# Raspberry_etherIO_v1.net
KiCad netlist of a schematic drawn in Altium Designer
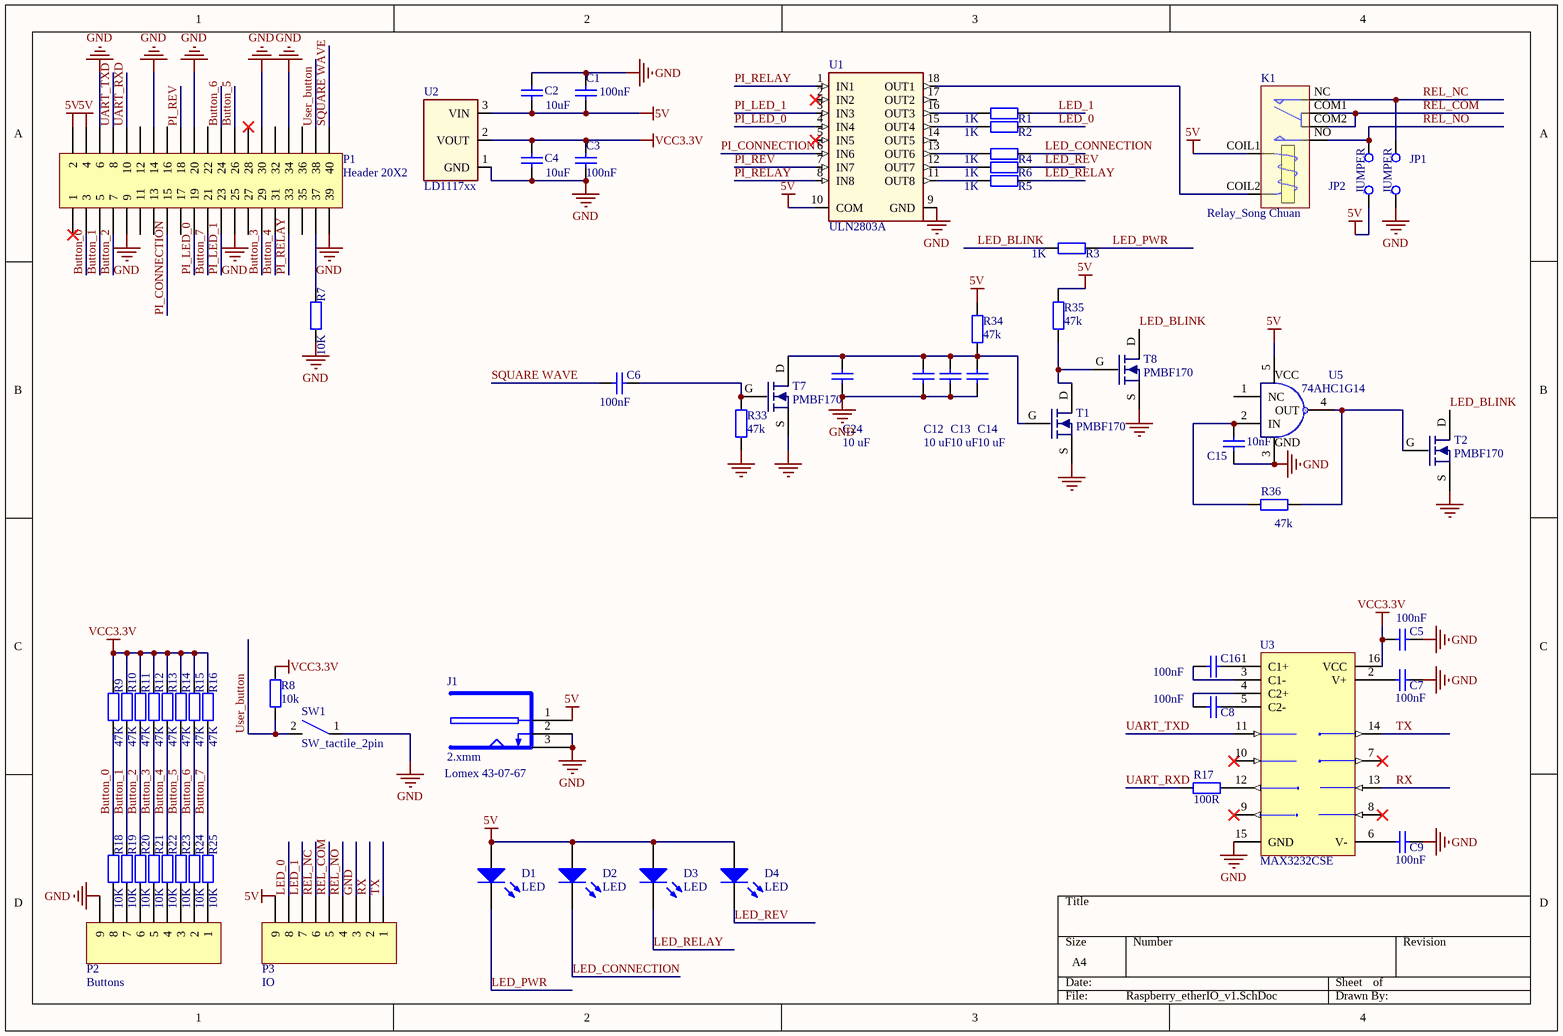
[diagram p0: Raspberry_etherIO_v1.SchDoc]

(export (version "E")
  (design (tool "Eeschema 10.0.6"))
  (components
    (comp (ref "C1")
      (value "100nF")
      (footprint "FP_0603_CAP_080")
      (description "Capacitor")
      (fields (field (name "PUBLISHER") "Altium Limited"))
      (libsource (lib "Miscellaneous Devices") (part "Cap"))
    )
    (comp (ref "C2")
      (value "10uF")
      (footprint "FP_1206_CAP_085")
      (description "Capacitor")
      (fields (field (name "PUBLISHER") "Altium Limited"))
      (libsource (lib "Miscellaneous Devices") (part "Cap"))
    )
    (comp (ref "C3")
      (value "100nF")
      (footprint "FP_0603_CAP_080")
      (description "Capacitor")
      (fields (field (name "PUBLISHER") "Altium Limited"))
      (libsource (lib "Miscellaneous Devices") (part "Cap"))
    )
    (comp (ref "C4")
      (value "10uF")
      (footprint "FP_1206_CAP_085")
      (description "Capacitor")
      (fields (field (name "PUBLISHER") "Altium Limited"))
      (libsource (lib "Miscellaneous Devices") (part "Cap"))
    )
    (comp (ref "C5")
      (value "100nF")
      (footprint "FP_0603_CAP_080")
      (description "Capacitor")
      (libsource (lib "Capacitor") (part "CAP"))
    )
    (comp (ref "C6")
      (value "100nF")
      (footprint "FP_0603_CAP_080")
      (description "Capacitor")
      (libsource (lib "Capacitor") (part "CAP"))
    )
    (comp (ref "C7")
      (value "100nF")
      (footprint "FP_0603_CAP_080")
      (description "Capacitor")
      (libsource (lib "Capacitor") (part "CAP"))
    )
    (comp (ref "C8")
      (value "100nF")
      (footprint "FP_0603_CAP_080")
      (description "Capacitor")
      (libsource (lib "Capacitor") (part "CAP"))
    )
    (comp (ref "C9")
      (value "100nF")
      (footprint "FP_0603_CAP_080")
      (description "Capacitor")
      (libsource (lib "Capacitor") (part "CAP"))
    )
    (comp (ref "C12")
      (value "10 uF")
      (footprint "FP_1210_CAP_N")
      (description "Capacitor")
      (libsource (lib "Capacitor") (part "CAP"))
    )
    (comp (ref "C13")
      (value "10 uF")
      (footprint "FP_1210_CAP_N")
      (description "Capacitor")
      (libsource (lib "Capacitor") (part "CAP"))
    )
    (comp (ref "C14")
      (value "10 uF")
      (footprint "FP_1210_CAP_N")
      (description "Capacitor")
      (libsource (lib "Capacitor") (part "CAP"))
    )
    (comp (ref "C15")
      (value "10nF")
      (footprint "FP_0603_CAP_080")
      (description "Capacitor")
      (fields (field (name "PUBLISHER") "Altium Limited"))
      (libsource (lib "Miscellaneous Devices") (part "Cap"))
    )
    (comp (ref "C16")
      (value "100nF")
      (footprint "FP_0603_CAP_080")
      (description "Capacitor")
      (libsource (lib "Capacitor") (part "CAP"))
    )
    (comp (ref "C24")
      (value "10 uF")
      (footprint "FP_1210_CAP_N")
      (description "Capacitor")
      (libsource (lib "Capacitor") (part "CAP"))
    )
    (comp (ref "D1")
      (value "LED")
      (footprint "1206 LED Reversed")
      (description "Typical LED")
      (libsource (lib "Led_optical") (part "LED"))
    )
    (comp (ref "D2")
      (value "LED")
      (footprint "1206 LED Reversed")
      (description "Typical LED")
      (libsource (lib "Led_optical") (part "LED"))
    )
    (comp (ref "D3")
      (value "LED")
      (footprint "1206 LED Reversed")
      (description "Typical LED")
      (libsource (lib "Led_optical") (part "LED"))
    )
    (comp (ref "D4")
      (value "LED")
      (footprint "1206 LED Reversed")
      (description "Typical LED")
      (libsource (lib "Led_optical") (part "LED"))
    )
    (comp (ref "J1")
      (value "2.xmm")
      (footprint "FP_DC_TAP_ANYA")
      (description "2.xmm DC HEBA25 TÁPFESZÜLTSÉG ALJZAT ZÁRT, NYÁKBA 90°")
      (fields (field (name "ORDER INFO") "Lomex 43-07-67"))
      (libsource (lib "Connector") (part "DC_TAP_ANYA"))
    )
    (comp (ref "JP1")
      (value "JUMPER")
      (footprint "FP_CONN2_TUSKE_254MM")
      (description "Jumper Wire")
      (libsource (lib "Other") (part "JUMPER"))
    )
    (comp (ref "JP2")
      (value "JUMPER")
      (footprint "FP_CONN2_TUSKE_254MM")
      (description "Jumper Wire")
      (libsource (lib "Other") (part "JUMPER"))
    )
    (comp (ref "K1")
      (value "Relay_Song Chuan")
      (footprint "Relay_Song Chuan")
      (description "SPDT Relay")
      (fields (field (name "PUBLISHER") "Altium Limited"))
      (libsource (lib "Switch") (part "Relay_Song Chuan"))
    )
    (comp (ref "P1")
      (value "Header 20X2")
      (footprint "Header_2X20_pin_2.54")
      (description "Header, 20-Pin, Dual row")
      (fields (field (name "PUBLISHER") "Altium Limited"))
      (libsource (lib "Miscellaneous Connectors") (part "Header 20X2"))
    )
    (comp (ref "P2")
      (value "Buttons")
      (footprint "Euroblock 3.5pitch 9P")
      (description "Header, 9-Pin")
      (fields (field (name "PUBLISHER") "Altium Limited"))
      (libsource (lib "Miscellaneous Connectors") (part "Header 9"))
    )
    (comp (ref "P3")
      (value "IO")
      (footprint "Euroblock 3.5pitch 9P")
      (description "Header, 9-Pin")
      (fields (field (name "PUBLISHER") "Altium Limited"))
      (libsource (lib "Miscellaneous Connectors") (part "Header 9"))
    )
    (comp (ref "R1")
      (value "1K")
      (footprint "FP_0603_RES")
      (description "Resistor")
      (libsource (lib "") (part "RES_2"))
    )
    (comp (ref "R2")
      (value "1K")
      (footprint "FP_0603_RES")
      (description "Resistor")
      (libsource (lib "") (part "RES_2"))
    )
    (comp (ref "R3")
      (value "1K")
      (footprint "FP_0603_RES")
      (description "Resistor")
      (libsource (lib "") (part "RES_2"))
    )
    (comp (ref "R4")
      (value "1K")
      (footprint "FP_0603_RES")
      (description "Resistor")
      (libsource (lib "") (part "RES_2"))
    )
    (comp (ref "R5")
      (value "1K")
      (footprint "FP_0603_RES")
      (description "Resistor")
      (libsource (lib "") (part "RES_2"))
    )
    (comp (ref "R6")
      (value "1K")
      (footprint "FP_0603_RES")
      (description "Resistor")
      (libsource (lib "") (part "RES_2"))
    )
    (comp (ref "R7")
      (value "10K")
      (footprint "FP_0603_RES")
      (description "Resistor")
      (libsource (lib "Resistor") (part "RES"))
    )
    (comp (ref "R8")
      (value "10k")
      (footprint "FP_0603_RES")
      (description "Resistor")
      (libsource (lib "") (part "RES_3"))
    )
    (comp (ref "R9")
      (value "47K")
      (footprint "FP_0603_RES")
      (description "Resistor")
      (libsource (lib "Resistor") (part "RES"))
    )
    (comp (ref "R10")
      (value "47K")
      (footprint "FP_0603_RES")
      (description "Resistor")
      (libsource (lib "Resistor") (part "RES"))
    )
    (comp (ref "R11")
      (value "47K")
      (footprint "FP_0603_RES")
      (description "Resistor")
      (libsource (lib "Resistor") (part "RES"))
    )
    (comp (ref "R12")
      (value "47K")
      (footprint "FP_0603_RES")
      (description "Resistor")
      (libsource (lib "Resistor") (part "RES"))
    )
    (comp (ref "R13")
      (value "47K")
      (footprint "FP_0603_RES")
      (description "Resistor")
      (libsource (lib "Resistor") (part "RES"))
    )
    (comp (ref "R14")
      (value "47K")
      (footprint "FP_0603_RES")
      (description "Resistor")
      (libsource (lib "Resistor") (part "RES"))
    )
    (comp (ref "R15")
      (value "47K")
      (footprint "FP_0603_RES")
      (description "Resistor")
      (libsource (lib "Resistor") (part "RES"))
    )
    (comp (ref "R16")
      (value "47K")
      (footprint "FP_0603_RES")
      (description "Resistor")
      (libsource (lib "Resistor") (part "RES"))
    )
    (comp (ref "R17")
      (value "100R")
      (footprint "FP_0603_RES")
      (description "Resistor")
      (libsource (lib "") (part "RES_1"))
    )
    (comp (ref "R18")
      (value "10K")
      (footprint "FP_0603_RES")
      (description "Resistor")
      (libsource (lib "Resistor") (part "RES"))
    )
    (comp (ref "R19")
      (value "10K")
      (footprint "FP_0603_RES")
      (description "Resistor")
      (libsource (lib "Resistor") (part "RES"))
    )
    (comp (ref "R20")
      (value "10K")
      (footprint "FP_0603_RES")
      (description "Resistor")
      (libsource (lib "Resistor") (part "RES"))
    )
    (comp (ref "R21")
      (value "10K")
      (footprint "FP_0603_RES")
      (description "Resistor")
      (libsource (lib "Resistor") (part "RES"))
    )
    (comp (ref "R22")
      (value "10K")
      (footprint "FP_0603_RES")
      (description "Resistor")
      (libsource (lib "Resistor") (part "RES"))
    )
    (comp (ref "R23")
      (value "10K")
      (footprint "FP_0603_RES")
      (description "Resistor")
      (libsource (lib "Resistor") (part "RES"))
    )
    (comp (ref "R24")
      (value "10K")
      (footprint "FP_0603_RES")
      (description "Resistor")
      (libsource (lib "Resistor") (part "RES"))
    )
    (comp (ref "R25")
      (value "10K")
      (footprint "FP_0603_RES")
      (description "Resistor")
      (libsource (lib "Resistor") (part "RES"))
    )
    (comp (ref "R33")
      (value "47k")
      (footprint "FP_0603_RES")
      (description "Resistor")
      (libsource (lib "Resistor") (part "RES"))
    )
    (comp (ref "R34")
      (value "47k")
      (footprint "FP_0603_RES")
      (description "Resistor")
      (libsource (lib "Resistor") (part "RES"))
    )
    (comp (ref "R35")
      (value "47k")
      (footprint "FP_0603_RES")
      (description "Resistor")
      (libsource (lib "Resistor") (part "RES"))
    )
    (comp (ref "R36")
      (value "47k")
      (footprint "FP_0603_RES")
      (description "Resistor")
      (fields (field (name "PUBLISHER") "Altium Limited"))
      (libsource (lib "Miscellaneous Devices") (part "Res3"))
    )
    (comp (ref "SW1")
      (value "SW_tactile_2pin")
      (footprint "SW_TACT_2PIN")
      (libsource (lib "Switch") (part "SW_tactile_2pin"))
    )
    (comp (ref "T1") (value "PMBF170") (footprint "FET_SOT23") (libsource (lib "FET") (part "NMOS")))
    (comp (ref "T2") (value "PMBF170") (footprint "FET_SOT23") (libsource (lib "FET") (part "NMOS")))
    (comp (ref "T7") (value "PMBF170") (footprint "FET_SOT23") (libsource (lib "FET") (part "NMOS")))
    (comp (ref "T8") (value "PMBF170") (footprint "FET_SOT23") (libsource (lib "FET") (part "NMOS")))
    (comp (ref "U1")
      (value "ULN2803A")
      (footprint "DIGITAL_SOIC18W")
      (libsource (lib "Digital") (part "ULN280x"))
    )
    (comp (ref "U2")
      (value "LD1117xx")
      (footprint "SUPPLY_SOT223")
      (description "LD1117xx 3,3V lin reg")
      (libsource (lib "Supply") (part "LD1117xx"))
    )
    (comp (ref "U3")
      (value "MAX3232CSE")
      (footprint "DIGITAL_SOIC16")
      (description "3.0V TO 5.5V, Low-Power, up to 1Mbps, True RS-232 Transceiver Using Four 0.1µF External Capacitor")
      (fields (field (name "PUBLISHER") "Altium Limited"))
      (libsource (lib "Maxim Communication Transceiver") (part "MAX3232CSE"))
    )
    (comp (ref "U5")
      (value "74AHC1G14")
      (footprint "GATE_SOT23-5")
      (description "SCHMITT-TRIGGER INVERTER")
      (libsource (lib "Logic_gate") (part "74AHC1G14"))
    )
  )
  (nets
    (net (code "1") (name "/Button_0") (class "Default")
      (node (ref "P1") (pin "3") (pinfunction "3_3") (pintype "passive"))
      (node (ref "R18") (pin "2") (pinfunction "2_2") (pintype "passive"))
      (node (ref "R9") (pin "1") (pinfunction "1_1") (pintype "passive"))
    )
    (net (code "2") (name "/Button_1") (class "Default")
      (node (ref "P1") (pin "5") (pinfunction "5_5") (pintype "passive"))
      (node (ref "R10") (pin "1") (pinfunction "1_1") (pintype "passive"))
      (node (ref "R19") (pin "2") (pinfunction "2_2") (pintype "passive"))
    )
    (net (code "3") (name "/Button_2") (class "Default")
      (node (ref "P1") (pin "7") (pinfunction "7_7") (pintype "passive"))
      (node (ref "R11") (pin "1") (pinfunction "1_1") (pintype "passive"))
      (node (ref "R20") (pin "2") (pinfunction "2_2") (pintype "passive"))
    )
    (net (code "4") (name "/Button_3") (class "Default")
      (node (ref "P1") (pin "29") (pinfunction "29_29") (pintype "passive"))
      (node (ref "R12") (pin "1") (pinfunction "1_1") (pintype "passive"))
      (node (ref "R21") (pin "2") (pinfunction "2_2") (pintype "passive"))
    )
    (net (code "5") (name "/Button_4") (class "Default")
      (node (ref "P1") (pin "31") (pinfunction "31_31") (pintype "passive"))
      (node (ref "R13") (pin "1") (pinfunction "1_1") (pintype "passive"))
      (node (ref "R22") (pin "2") (pinfunction "2_2") (pintype "passive"))
    )
    (net (code "6") (name "/Button_5") (class "Default")
      (node (ref "P1") (pin "26") (pinfunction "26_26") (pintype "passive"))
      (node (ref "R14") (pin "1") (pinfunction "1_1") (pintype "passive"))
      (node (ref "R23") (pin "2") (pinfunction "2_2") (pintype "passive"))
    )
    (net (code "7") (name "/Button_6") (class "Default")
      (node (ref "P1") (pin "24") (pinfunction "24_24") (pintype "passive"))
      (node (ref "R15") (pin "1") (pinfunction "1_1") (pintype "passive"))
      (node (ref "R24") (pin "2") (pinfunction "2_2") (pintype "passive"))
    )
    (net (code "8") (name "/Button_7") (class "Default")
      (node (ref "P1") (pin "21") (pinfunction "21_21") (pintype "passive"))
      (node (ref "R16") (pin "1") (pinfunction "1_1") (pintype "passive"))
      (node (ref "R25") (pin "2") (pinfunction "2_2") (pintype "passive"))
    )
    (net (code "9") (name "/LED_0") (class "Default")
      (node (ref "P3") (pin "8") (pinfunction "8_8") (pintype "passive"))
      (node (ref "R2") (pin "2") (pinfunction "2_2") (pintype "passive"))
    )
    (net (code "10") (name "/LED_1") (class "Default")
      (node (ref "P3") (pin "7") (pinfunction "7_7") (pintype "passive"))
      (node (ref "R1") (pin "2") (pinfunction "2_2") (pintype "passive"))
    )
    (net (code "11") (name "/LED_BLINK") (class "Default")
      (node (ref "R3") (pin "1") (pinfunction "1_1") (pintype "passive"))
      (node (ref "T2") (pin "D") (pinfunction "D_D") (pintype "passive"))
      (node (ref "T8") (pin "D") (pinfunction "D_D") (pintype "passive"))
    )
    (net (code "12") (name "/LED_CONNECTION") (class "Default")
      (node (ref "D2") (pin "2") (pinfunction "K_2") (pintype "passive"))
      (node (ref "R4") (pin "2") (pinfunction "2_2") (pintype "passive"))
    )
    (net (code "13") (name "/LED_PWR") (class "Default")
      (node (ref "D1") (pin "2") (pinfunction "K_2") (pintype "passive"))
      (node (ref "R3") (pin "2") (pinfunction "2_2") (pintype "passive"))
    )
    (net (code "14") (name "/LED_RELAY") (class "Default")
      (node (ref "D3") (pin "2") (pinfunction "K_2") (pintype "passive"))
      (node (ref "R5") (pin "2") (pinfunction "2_2") (pintype "passive"))
    )
    (net (code "15") (name "/LED_REV") (class "Default")
      (node (ref "D4") (pin "2") (pinfunction "K_2") (pintype "passive"))
      (node (ref "R6") (pin "2") (pinfunction "2_2") (pintype "passive"))
    )
    (net (code "16") (name "/PI_CONNECTION") (class "Default")
      (node (ref "P1") (pin "15") (pinfunction "15_15") (pintype "passive"))
      (node (ref "U1") (pin "6") (pinfunction "IN6_6") (pintype "input"))
    )
    (net (code "17") (name "/PI_LED_0") (class "Default")
      (node (ref "P1") (pin "19") (pinfunction "19_19") (pintype "passive"))
      (node (ref "U1") (pin "4") (pinfunction "IN4_4") (pintype "input"))
    )
    (net (code "18") (name "/PI_LED_1") (class "Default")
      (node (ref "P1") (pin "23") (pinfunction "23_23") (pintype "passive"))
      (node (ref "U1") (pin "3") (pinfunction "IN3_3") (pintype "input"))
    )
    (net (code "19") (name "/PI_RELAY") (class "Default")
      (node (ref "P1") (pin "33") (pinfunction "33_33") (pintype "passive"))
      (node (ref "U1") (pin "1") (pinfunction "IN1_1") (pintype "input"))
      (node (ref "U1") (pin "8") (pinfunction "IN8_8") (pintype "input"))
    )
    (net (code "20") (name "/PI_REV") (class "Default")
      (node (ref "P1") (pin "18") (pinfunction "18_18") (pintype "passive"))
      (node (ref "U1") (pin "7") (pinfunction "IN7_7") (pintype "input"))
    )
    (net (code "21") (name "/REL_COM") (class "Default")
      (node (ref "K1") (pin "COM1") (pinfunction "COM_COM1") (pintype "passive"))
      (node (ref "K1") (pin "COM2") (pinfunction "COM_COM2") (pintype "passive"))
      (node (ref "P3") (pin "5") (pinfunction "5_5") (pintype "passive"))
    )
    (net (code "22") (name "/REL_NC") (class "Default")
      (node (ref "JP1") (pin "2") (pinfunction "C2_2") (pintype "passive"))
      (node (ref "K1") (pin "NC") (pinfunction "NC_NC") (pintype "passive"))
      (node (ref "P3") (pin "6") (pinfunction "6_6") (pintype "passive"))
    )
    (net (code "23") (name "/REL_NO") (class "Default")
      (node (ref "JP2") (pin "2") (pinfunction "C2_2") (pintype "passive"))
      (node (ref "K1") (pin "NO") (pinfunction "NO_NO") (pintype "passive"))
      (node (ref "P3") (pin "4") (pinfunction "4_4") (pintype "passive"))
    )
    (net (code "24") (name "/RX") (class "Default")
      (node (ref "P3") (pin "2") (pinfunction "2_2") (pintype "passive"))
      (node (ref "U3") (pin "13") (pinfunction "R1IN_13") (pintype "input"))
    )
    (net (code "25") (name "/SQUARE WAVE") (class "Default")
      (node (ref "C6") (pin "1") (pinfunction "1_1") (pintype "passive"))
      (node (ref "P1") (pin "40") (pinfunction "40_40") (pintype "passive"))
    )
    (net (code "26") (name "/TX") (class "Default")
      (node (ref "P3") (pin "1") (pinfunction "1_1") (pintype "passive"))
      (node (ref "U3") (pin "14") (pinfunction "T1OUT_14") (pintype "output"))
    )
    (net (code "27") (name "/UART_RXD") (class "Default")
      (node (ref "P1") (pin "10") (pinfunction "10_10") (pintype "passive"))
      (node (ref "R17") (pin "2") (pinfunction "2_2") (pintype "passive"))
    )
    (net (code "28") (name "/UART_TXD") (class "Default")
      (node (ref "P1") (pin "8") (pinfunction "8_8") (pintype "passive"))
      (node (ref "U3") (pin "11") (pinfunction "T1IN_11") (pintype "input"))
    )
    (net (code "29") (name "/User_button") (class "Default")
      (node (ref "P1") (pin "38") (pinfunction "38_38") (pintype "passive"))
      (node (ref "R8") (pin "2") (pinfunction "2_2") (pintype "passive"))
      (node (ref "SW1") (pin "2") (pinfunction "2_2") (pintype "passive"))
    )
    (net (code "30") (name "5V") (class "Default")
      (node (ref "C1") (pin "2") (pinfunction "2_2") (pintype "passive"))
      (node (ref "C2") (pin "1") (pinfunction "1_1") (pintype "passive"))
      (node (ref "D1") (pin "1") (pinfunction "A_1") (pintype "passive"))
      (node (ref "D2") (pin "1") (pinfunction "A_1") (pintype "passive"))
      (node (ref "D3") (pin "1") (pinfunction "A_1") (pintype "passive"))
      (node (ref "D4") (pin "1") (pinfunction "A_1") (pintype "passive"))
      (node (ref "J1") (pin "1") (pinfunction "9V_1") (pintype "power_in"))
      (node (ref "JP2") (pin "1") (pinfunction "C1_1") (pintype "passive"))
      (node (ref "K1") (pin "COIL1") (pinfunction "COIL1_COIL1") (pintype "passive"))
      (node (ref "P1") (pin "2") (pinfunction "2_2") (pintype "passive"))
      (node (ref "P1") (pin "4") (pinfunction "4_4") (pintype "passive"))
      (node (ref "P3") (pin "9") (pinfunction "9_9") (pintype "passive"))
      (node (ref "R34") (pin "2") (pinfunction "2_2") (pintype "passive"))
      (node (ref "R35") (pin "2") (pinfunction "2_2") (pintype "passive"))
      (node (ref "U1") (pin "10") (pinfunction "COM_10") (pintype "passive"))
      (node (ref "U2") (pin "3") (pinfunction "VIN_3") (pintype "passive"))
      (node (ref "U5") (pin "5") (pinfunction "VCC_5") (pintype "passive"))
    )
    (net (code "31") (name "GND") (class "Default")
      (node (ref "C1") (pin "1") (pinfunction "1_1") (pintype "passive"))
      (node (ref "C12") (pin "1") (pinfunction "1_1") (pintype "passive"))
      (node (ref "C13") (pin "1") (pinfunction "1_1") (pintype "passive"))
      (node (ref "C14") (pin "1") (pinfunction "1_1") (pintype "passive"))
      (node (ref "C15") (pin "1") (pinfunction "1_1") (pintype "passive"))
      (node (ref "C2") (pin "2") (pinfunction "2_2") (pintype "passive"))
      (node (ref "C24") (pin "1") (pinfunction "1_1") (pintype "passive"))
      (node (ref "C3") (pin "2") (pinfunction "2_2") (pintype "passive"))
      (node (ref "C4") (pin "1") (pinfunction "1_1") (pintype "passive"))
      (node (ref "C5") (pin "2") (pinfunction "2_2") (pintype "passive"))
      (node (ref "C7") (pin "2") (pinfunction "2_2") (pintype "passive"))
      (node (ref "C9") (pin "2") (pinfunction "2_2") (pintype "passive"))
      (node (ref "J1") (pin "2") (pinfunction "GND_2") (pintype "power_in"))
      (node (ref "J1") (pin "3") (pinfunction "GND_3") (pintype "power_in"))
      (node (ref "JP1") (pin "1") (pinfunction "C1_1") (pintype "passive"))
      (node (ref "P1") (pin "14") (pinfunction "14_14") (pintype "passive"))
      (node (ref "P1") (pin "20") (pinfunction "20_20") (pintype "passive"))
      (node (ref "P1") (pin "25") (pinfunction "25_25") (pintype "passive"))
      (node (ref "P1") (pin "30") (pinfunction "30_30") (pintype "passive"))
      (node (ref "P1") (pin "34") (pinfunction "34_34") (pintype "passive"))
      (node (ref "P1") (pin "39") (pinfunction "39_39") (pintype "passive"))
      (node (ref "P1") (pin "6") (pinfunction "6_6") (pintype "passive"))
      (node (ref "P1") (pin "9") (pinfunction "9_9") (pintype "passive"))
      (node (ref "P2") (pin "9") (pinfunction "9_9") (pintype "passive"))
      (node (ref "P3") (pin "3") (pinfunction "3_3") (pintype "passive"))
      (node (ref "R33") (pin "1") (pinfunction "1_1") (pintype "passive"))
      (node (ref "R7") (pin "1") (pinfunction "1_1") (pintype "passive"))
      (node (ref "SW1") (pin "1") (pinfunction "1_1") (pintype "passive"))
      (node (ref "T1") (pin "S") (pinfunction "S_S") (pintype "passive"))
      (node (ref "T2") (pin "S") (pinfunction "S_S") (pintype "passive"))
      (node (ref "T7") (pin "S") (pinfunction "S_S") (pintype "passive"))
      (node (ref "T8") (pin "S") (pinfunction "S_S") (pintype "passive"))
      (node (ref "U1") (pin "9") (pinfunction "GND_9") (pintype "power_in"))
      (node (ref "U2") (pin "1") (pinfunction "GND_1") (pintype "passive"))
      (node (ref "U3") (pin "15") (pinfunction "GND_15") (pintype "power_in"))
      (node (ref "U5") (pin "3") (pinfunction "GND_3") (pintype "passive"))
    )
    (net (code "32") (name "Net-(C6-Pad2)") (class "Default")
      (node (ref "C6") (pin "2") (pinfunction "2_2") (pintype "passive"))
      (node (ref "R33") (pin "2") (pinfunction "2_2") (pintype "passive"))
      (node (ref "T7") (pin "G") (pinfunction "G_G") (pintype "passive"))
    )
    (net (code "33") (name "Net-(C12-Pad2)") (class "Default")
      (node (ref "C12") (pin "2") (pinfunction "2_2") (pintype "passive"))
      (node (ref "C13") (pin "2") (pinfunction "2_2") (pintype "passive"))
      (node (ref "C14") (pin "2") (pinfunction "2_2") (pintype "passive"))
      (node (ref "C24") (pin "2") (pinfunction "2_2") (pintype "passive"))
      (node (ref "R34") (pin "1") (pinfunction "1_1") (pintype "passive"))
      (node (ref "T1") (pin "G") (pinfunction "G_G") (pintype "passive"))
      (node (ref "T7") (pin "D") (pinfunction "D_D") (pintype "passive"))
    )
    (net (code "34") (name "Net-(P1-Pad37)") (class "Default")
      (node (ref "P1") (pin "37") (pinfunction "37_37") (pintype "passive"))
      (node (ref "R7") (pin "2") (pinfunction "2_2") (pintype "passive"))
    )
    (net (code "35") (name "Net-(P2-Pad1)") (class "Default")
      (node (ref "P2") (pin "1") (pinfunction "1_1") (pintype "passive"))
      (node (ref "R25") (pin "1") (pinfunction "1_1") (pintype "passive"))
    )
    (net (code "36") (name "Net-(P2-Pad2)") (class "Default")
      (node (ref "P2") (pin "2") (pinfunction "2_2") (pintype "passive"))
      (node (ref "R24") (pin "1") (pinfunction "1_1") (pintype "passive"))
    )
    (net (code "37") (name "Net-(P2-Pad3)") (class "Default")
      (node (ref "P2") (pin "3") (pinfunction "3_3") (pintype "passive"))
      (node (ref "R23") (pin "1") (pinfunction "1_1") (pintype "passive"))
    )
    (net (code "38") (name "Net-(P2-Pad4)") (class "Default")
      (node (ref "P2") (pin "4") (pinfunction "4_4") (pintype "passive"))
      (node (ref "R22") (pin "1") (pinfunction "1_1") (pintype "passive"))
    )
    (net (code "39") (name "Net-(P2-Pad5)") (class "Default")
      (node (ref "P2") (pin "5") (pinfunction "5_5") (pintype "passive"))
      (node (ref "R21") (pin "1") (pinfunction "1_1") (pintype "passive"))
    )
    (net (code "40") (name "Net-(P2-Pad6)") (class "Default")
      (node (ref "P2") (pin "6") (pinfunction "6_6") (pintype "passive"))
      (node (ref "R20") (pin "1") (pinfunction "1_1") (pintype "passive"))
    )
    (net (code "41") (name "Net-(P2-Pad7)") (class "Default")
      (node (ref "P2") (pin "7") (pinfunction "7_7") (pintype "passive"))
      (node (ref "R19") (pin "1") (pinfunction "1_1") (pintype "passive"))
    )
    (net (code "42") (name "Net-(P2-Pad8)") (class "Default")
      (node (ref "P2") (pin "8") (pinfunction "8_8") (pintype "passive"))
      (node (ref "R18") (pin "1") (pinfunction "1_1") (pintype "passive"))
    )
    (net (code "43") (name "Net-(R35-Pad1)") (class "Default")
      (node (ref "R35") (pin "1") (pinfunction "1_1") (pintype "passive"))
      (node (ref "T1") (pin "D") (pinfunction "D_D") (pintype "passive"))
      (node (ref "T8") (pin "G") (pinfunction "G_G") (pintype "passive"))
    )
    (net (code "44") (name "Net-(U1-OUT1)") (class "Default")
      (node (ref "K1") (pin "COIL2") (pinfunction "COIL2_COIL2") (pintype "passive"))
      (node (ref "U1") (pin "18") (pinfunction "OUT1_18") (pintype "output"))
    )
    (net (code "45") (name "Net-(U1-OUT3)") (class "Default")
      (node (ref "R1") (pin "1") (pinfunction "1_1") (pintype "passive"))
      (node (ref "U1") (pin "16") (pinfunction "OUT3_16") (pintype "output"))
    )
    (net (code "46") (name "Net-(U1-OUT4)") (class "Default")
      (node (ref "R2") (pin "1") (pinfunction "1_1") (pintype "passive"))
      (node (ref "U1") (pin "15") (pinfunction "OUT4_15") (pintype "output"))
    )
    (net (code "47") (name "Net-(U1-OUT6)") (class "Default")
      (node (ref "R4") (pin "1") (pinfunction "1_1") (pintype "passive"))
      (node (ref "U1") (pin "13") (pinfunction "OUT6_13") (pintype "output"))
    )
    (net (code "48") (name "Net-(U1-OUT7)") (class "Default")
      (node (ref "R6") (pin "1") (pinfunction "1_1") (pintype "passive"))
      (node (ref "U1") (pin "12") (pinfunction "OUT7_12") (pintype "output"))
    )
    (net (code "49") (name "Net-(U1-OUT8)") (class "Default")
      (node (ref "R5") (pin "1") (pinfunction "1_1") (pintype "passive"))
      (node (ref "U1") (pin "11") (pinfunction "OUT8_11") (pintype "output"))
    )
    (net (code "50") (name "Net-(U3-C1+)") (class "Default")
      (node (ref "C16") (pin "2") (pinfunction "2_2") (pintype "passive"))
      (node (ref "U3") (pin "1") (pinfunction "C1+_1") (pintype "passive"))
    )
    (net (code "51") (name "Net-(U3-C1-)") (class "Default")
      (node (ref "C16") (pin "1") (pinfunction "1_1") (pintype "passive"))
      (node (ref "U3") (pin "3") (pinfunction "C1-_3") (pintype "passive"))
    )
    (net (code "52") (name "Net-(U3-C2+)") (class "Default")
      (node (ref "C8") (pin "1") (pinfunction "1_1") (pintype "passive"))
      (node (ref "U3") (pin "4") (pinfunction "C2+_4") (pintype "passive"))
    )
    (net (code "53") (name "Net-(U3-C2-)") (class "Default")
      (node (ref "C8") (pin "2") (pinfunction "2_2") (pintype "passive"))
      (node (ref "U3") (pin "5") (pinfunction "C2-_5") (pintype "passive"))
    )
    (net (code "54") (name "Net-(U3-R1OUT)") (class "Default")
      (node (ref "R17") (pin "1") (pinfunction "1_1") (pintype "passive"))
      (node (ref "U3") (pin "12") (pinfunction "R1OUT_12") (pintype "output"))
    )
    (net (code "55") (name "Net-(U3-V+)") (class "Default")
      (node (ref "C7") (pin "1") (pinfunction "1_1") (pintype "passive"))
      (node (ref "U3") (pin "2") (pinfunction "V+_2") (pintype "power_in"))
    )
    (net (code "56") (name "Net-(U3-V-)") (class "Default")
      (node (ref "C9") (pin "1") (pinfunction "1_1") (pintype "passive"))
      (node (ref "U3") (pin "6") (pinfunction "V-_6") (pintype "power_in"))
    )
    (net (code "57") (name "Net-(U5-IN)") (class "Default")
      (node (ref "C15") (pin "2") (pinfunction "2_2") (pintype "passive"))
      (node (ref "R36") (pin "2") (pinfunction "2_2") (pintype "passive"))
      (node (ref "U5") (pin "2") (pinfunction "IN_2") (pintype "passive"))
    )
    (net (code "58") (name "Net-(U5-OUT)") (class "Default")
      (node (ref "R36") (pin "1") (pinfunction "1_1") (pintype "passive"))
      (node (ref "T2") (pin "G") (pinfunction "G_G") (pintype "passive"))
      (node (ref "U5") (pin "4") (pinfunction "OUT_4") (pintype "passive"))
    )
    (net (code "59") (name "VCC3.3V") (class "Default")
      (node (ref "C3") (pin "1") (pinfunction "1_1") (pintype "passive"))
      (node (ref "C4") (pin "2") (pinfunction "2_2") (pintype "passive"))
      (node (ref "C5") (pin "1") (pinfunction "1_1") (pintype "passive"))
      (node (ref "R10") (pin "2") (pinfunction "2_2") (pintype "passive"))
      (node (ref "R11") (pin "2") (pinfunction "2_2") (pintype "passive"))
      (node (ref "R12") (pin "2") (pinfunction "2_2") (pintype "passive"))
      (node (ref "R13") (pin "2") (pinfunction "2_2") (pintype "passive"))
      (node (ref "R14") (pin "2") (pinfunction "2_2") (pintype "passive"))
      (node (ref "R15") (pin "2") (pinfunction "2_2") (pintype "passive"))
      (node (ref "R16") (pin "2") (pinfunction "2_2") (pintype "passive"))
      (node (ref "R8") (pin "1") (pinfunction "1_1") (pintype "passive"))
      (node (ref "R9") (pin "2") (pinfunction "2_2") (pintype "passive"))
      (node (ref "U2") (pin "2") (pinfunction "VOUT_2") (pintype "passive"))
      (node (ref "U3") (pin "16") (pinfunction "VCC_16") (pintype "power_in"))
    )
    (net (code "60") (name "unconnected-(P1-Pad1)") (class "Default")
      (node (ref "P1") (pin "1") (pinfunction "1_1") (pintype "passive+no_connect"))
    )
    (net (code "61") (name "unconnected-(P1-Pad11)") (class "Default")
      (node (ref "P1") (pin "11") (pinfunction "11_11") (pintype "passive"))
    )
    (net (code "62") (name "unconnected-(P1-Pad12)") (class "Default")
      (node (ref "P1") (pin "12") (pinfunction "12_12") (pintype "passive"))
    )
    (net (code "63") (name "unconnected-(P1-Pad13)") (class "Default")
      (node (ref "P1") (pin "13") (pinfunction "13_13") (pintype "passive"))
    )
    (net (code "64") (name "unconnected-(P1-Pad16)") (class "Default")
      (node (ref "P1") (pin "16") (pinfunction "16_16") (pintype "passive"))
    )
    (net (code "65") (name "unconnected-(P1-Pad17)") (class "Default")
      (node (ref "P1") (pin "17") (pinfunction "17_17") (pintype "passive"))
    )
    (net (code "66") (name "unconnected-(P1-Pad22)") (class "Default")
      (node (ref "P1") (pin "22") (pinfunction "22_22") (pintype "passive"))
    )
    (net (code "67") (name "unconnected-(P1-Pad27)") (class "Default")
      (node (ref "P1") (pin "27") (pinfunction "27_27") (pintype "passive"))
    )
    (net (code "68") (name "unconnected-(P1-Pad28)") (class "Default")
      (node (ref "P1") (pin "28") (pinfunction "28_28") (pintype "passive+no_connect"))
    )
    (net (code "69") (name "unconnected-(P1-Pad32)") (class "Default")
      (node (ref "P1") (pin "32") (pinfunction "32_32") (pintype "passive"))
    )
    (net (code "70") (name "unconnected-(P1-Pad35)") (class "Default")
      (node (ref "P1") (pin "35") (pinfunction "35_35") (pintype "passive"))
    )
    (net (code "71") (name "unconnected-(P1-Pad36)") (class "Default")
      (node (ref "P1") (pin "36") (pinfunction "36_36") (pintype "passive"))
    )
    (net (code "72") (name "unconnected-(U1-IN2-Pad2)") (class "Default")
      (node (ref "U1") (pin "2") (pinfunction "IN2_2") (pintype "input+no_connect"))
    )
    (net (code "73") (name "unconnected-(U1-IN5-Pad5)") (class "Default")
      (node (ref "U1") (pin "5") (pinfunction "IN5_5") (pintype "input+no_connect"))
    )
    (net (code "74") (name "unconnected-(U1-OUT2-Pad17)") (class "Default")
      (node (ref "U1") (pin "17") (pinfunction "OUT2_17") (pintype "output"))
    )
    (net (code "75") (name "unconnected-(U1-OUT5-Pad14)") (class "Default")
      (node (ref "U1") (pin "14") (pinfunction "OUT5_14") (pintype "output"))
    )
    (net (code "76") (name "unconnected-(U3-R2IN-Pad8)") (class "Default")
      (node (ref "U3") (pin "8") (pinfunction "R2IN_8") (pintype "input+no_connect"))
    )
    (net (code "77") (name "unconnected-(U3-R2OUT-Pad9)") (class "Default")
      (node (ref "U3") (pin "9") (pinfunction "R2OUT_9") (pintype "output+no_connect"))
    )
    (net (code "78") (name "unconnected-(U3-T2IN-Pad10)") (class "Default")
      (node (ref "U3") (pin "10") (pinfunction "T2IN_10") (pintype "input+no_connect"))
    )
    (net (code "79") (name "unconnected-(U3-T2OUT-Pad7)") (class "Default")
      (node (ref "U3") (pin "7") (pinfunction "T2OUT_7") (pintype "output+no_connect"))
    )
    (net (code "80") (name "unconnected-(U5-NC-Pad1)") (class "Default")
      (node (ref "U5") (pin "1") (pinfunction "NC_1") (pintype "passive"))
    )
  )
)
